# md_modularf.net
KiCad netlist of a schematic drawn in EAGLE
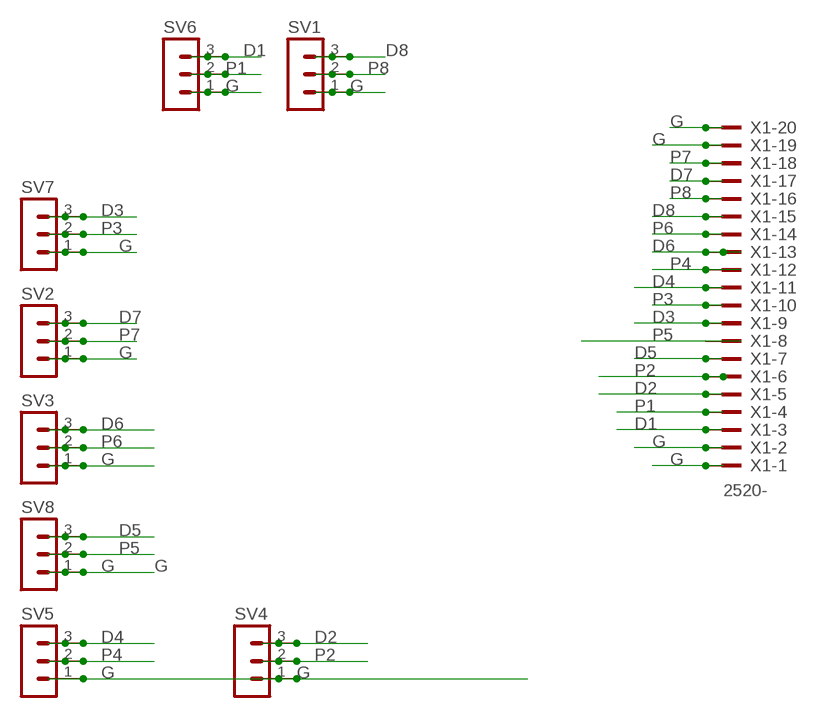
[diagram p0: schematic, sheet 1]

(export (version "E")
  (design (tool "Eeschema 10.0.6"))
  (components
    (comp (ref "SV1")
      (value "MA03-1")
      (footprint "eagle-import:MA03-1")
      (libsource (lib "eagle-import") (part "MA03-1"))
    )
    (comp (ref "SV2")
      (value "MA03-1")
      (footprint "eagle-import:MA03-1")
      (libsource (lib "eagle-import") (part "MA03-1"))
    )
    (comp (ref "SV3")
      (value "MA03-1")
      (footprint "eagle-import:MA03-1")
      (libsource (lib "eagle-import") (part "MA03-1"))
    )
    (comp (ref "SV4")
      (value "MA03-1")
      (footprint "eagle-import:MA03-1")
      (libsource (lib "eagle-import") (part "MA03-1"))
    )
    (comp (ref "SV5")
      (value "MA03-1")
      (footprint "eagle-import:MA03-1")
      (libsource (lib "eagle-import") (part "MA03-1"))
    )
    (comp (ref "SV6")
      (value "MA03-1")
      (footprint "eagle-import:MA03-1")
      (libsource (lib "eagle-import") (part "MA03-1"))
    )
    (comp (ref "SV7")
      (value "MA03-1")
      (footprint "eagle-import:MA03-1")
      (libsource (lib "eagle-import") (part "MA03-1"))
    )
    (comp (ref "SV8")
      (value "MA03-1")
      (footprint "eagle-import:MA03-1")
      (libsource (lib "eagle-import") (part "MA03-1"))
    )
    (comp (ref "X1")
      (value "2520-")
      (footprint "eagle-import:PAK100_2500-20")
      (libsource (lib "eagle-import") (part "2520-"))
    )
  )
  (nets
    (net (code "1") (name "/D1") (class "Default")
      (node (ref "SV6") (pin "3") (pinfunction "3_3") (pintype "passive"))
      (node (ref "X1") (pin "3") (pinfunction "KL_3") (pintype "passive"))
    )
    (net (code "2") (name "/D2") (class "Default")
      (node (ref "SV4") (pin "3") (pinfunction "3_3") (pintype "passive"))
      (node (ref "X1") (pin "5") (pinfunction "KL_5") (pintype "passive"))
    )
    (net (code "3") (name "/D3") (class "Default")
      (node (ref "SV7") (pin "3") (pinfunction "3_3") (pintype "passive"))
      (node (ref "X1") (pin "9") (pinfunction "KL_9") (pintype "passive"))
    )
    (net (code "4") (name "/D4") (class "Default")
      (node (ref "SV5") (pin "3") (pinfunction "3_3") (pintype "passive"))
      (node (ref "X1") (pin "11") (pinfunction "KL_11") (pintype "passive"))
    )
    (net (code "5") (name "/D5") (class "Default")
      (node (ref "SV8") (pin "3") (pinfunction "3_3") (pintype "passive"))
      (node (ref "X1") (pin "7") (pinfunction "KL_7") (pintype "passive"))
    )
    (net (code "6") (name "/D6") (class "Default")
      (node (ref "SV3") (pin "3") (pinfunction "3_3") (pintype "passive"))
      (node (ref "X1") (pin "13") (pinfunction "KL_13") (pintype "passive"))
    )
    (net (code "7") (name "/D7") (class "Default")
      (node (ref "SV2") (pin "3") (pinfunction "3_3") (pintype "passive"))
      (node (ref "X1") (pin "17") (pinfunction "KL_17") (pintype "passive"))
    )
    (net (code "8") (name "/D8") (class "Default")
      (node (ref "SV1") (pin "3") (pinfunction "3_3") (pintype "passive"))
      (node (ref "X1") (pin "15") (pinfunction "KL_15") (pintype "passive"))
    )
    (net (code "9") (name "/G") (class "Default")
      (node (ref "SV1") (pin "1") (pinfunction "1_1") (pintype "passive"))
      (node (ref "SV2") (pin "1") (pinfunction "1_1") (pintype "passive"))
      (node (ref "SV3") (pin "1") (pinfunction "1_1") (pintype "passive"))
      (node (ref "SV4") (pin "1") (pinfunction "1_1") (pintype "passive"))
      (node (ref "SV5") (pin "1") (pinfunction "1_1") (pintype "passive"))
      (node (ref "SV6") (pin "1") (pinfunction "1_1") (pintype "passive"))
      (node (ref "SV7") (pin "1") (pinfunction "1_1") (pintype "passive"))
      (node (ref "SV8") (pin "1") (pinfunction "1_1") (pintype "passive"))
      (node (ref "X1") (pin "1") (pinfunction "KL_1") (pintype "passive"))
      (node (ref "X1") (pin "19") (pinfunction "KL_19") (pintype "passive"))
      (node (ref "X1") (pin "2") (pinfunction "KL_2") (pintype "passive"))
      (node (ref "X1") (pin "20") (pinfunction "KL_20") (pintype "passive"))
    )
    (net (code "10") (name "/P1") (class "Default")
      (node (ref "SV6") (pin "2") (pinfunction "2_2") (pintype "passive"))
      (node (ref "X1") (pin "4") (pinfunction "KL_4") (pintype "passive"))
    )
    (net (code "11") (name "/P2") (class "Default")
      (node (ref "SV4") (pin "2") (pinfunction "2_2") (pintype "passive"))
      (node (ref "X1") (pin "6") (pinfunction "KL_6") (pintype "passive"))
    )
    (net (code "12") (name "/P3") (class "Default")
      (node (ref "SV7") (pin "2") (pinfunction "2_2") (pintype "passive"))
      (node (ref "X1") (pin "10") (pinfunction "KL_10") (pintype "passive"))
    )
    (net (code "13") (name "/P4") (class "Default")
      (node (ref "SV5") (pin "2") (pinfunction "2_2") (pintype "passive"))
      (node (ref "X1") (pin "12") (pinfunction "KL_12") (pintype "passive"))
    )
    (net (code "14") (name "/P5") (class "Default")
      (node (ref "SV8") (pin "2") (pinfunction "2_2") (pintype "passive"))
      (node (ref "X1") (pin "8") (pinfunction "KL_8") (pintype "passive"))
    )
    (net (code "15") (name "/P6") (class "Default")
      (node (ref "SV3") (pin "2") (pinfunction "2_2") (pintype "passive"))
      (node (ref "X1") (pin "14") (pinfunction "KL_14") (pintype "passive"))
    )
    (net (code "16") (name "/P7") (class "Default")
      (node (ref "SV2") (pin "2") (pinfunction "2_2") (pintype "passive"))
      (node (ref "X1") (pin "18") (pinfunction "KL_18") (pintype "passive"))
    )
    (net (code "17") (name "/P8") (class "Default")
      (node (ref "SV1") (pin "2") (pinfunction "2_2") (pintype "passive"))
      (node (ref "X1") (pin "16") (pinfunction "KL_16") (pintype "passive"))
    )
  )
)
